# Calc_V1.net
KiCad netlist of a schematic drawn in Altium Designer
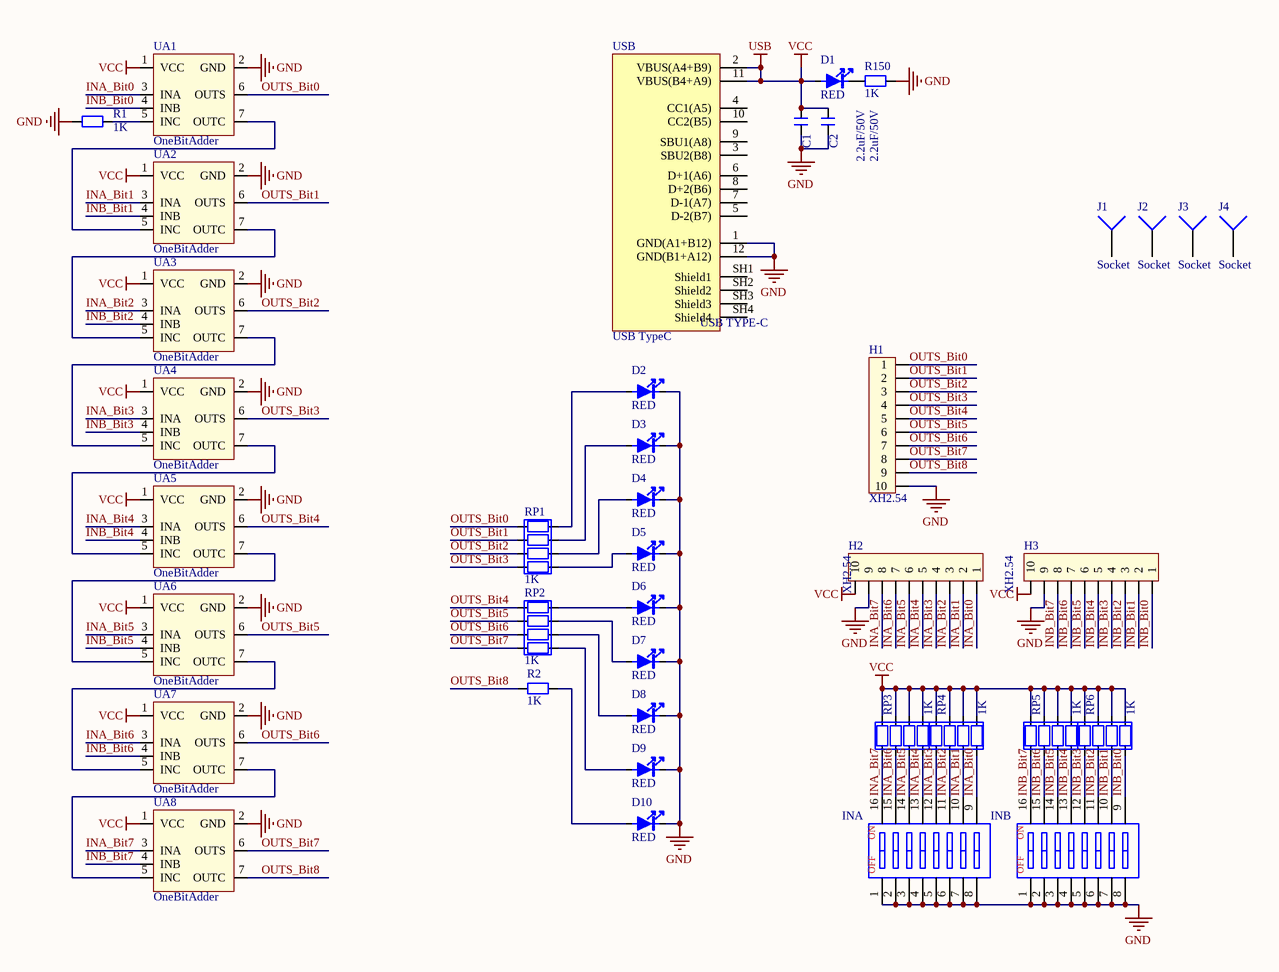
[diagram p0: Calc_V1.SchDoc]

(export (version "E")
  (design (tool "Eeschema 10.0.6"))
  (components
    (comp (ref "C1")
      (value "2.2uF/50V")
      (footprint "C 0603_L")
      (description "无极性贴片电容")
      (libsource (lib "LovelessingSch") (part "C"))
    )
    (comp (ref "C2")
      (value "2.2uF/50V")
      (footprint "C 0603_L")
      (description "无极性贴片电容")
      (libsource (lib "LovelessingSch") (part "C"))
    )
    (comp (ref "D1")
      (value "RED")
      (footprint "LED 0603B")
      (description "发光二极管")
      (libsource (lib "LovelessingSch") (part "LED"))
    )
    (comp (ref "D2")
      (value "RED")
      (footprint "LED 0603B")
      (description "发光二极管")
      (libsource (lib "LovelessingSch") (part "LED"))
    )
    (comp (ref "D3")
      (value "RED")
      (footprint "LED 0603B")
      (description "发光二极管")
      (libsource (lib "LovelessingSch") (part "LED"))
    )
    (comp (ref "D4")
      (value "RED")
      (footprint "LED 0603B")
      (description "发光二极管")
      (libsource (lib "LovelessingSch") (part "LED"))
    )
    (comp (ref "D5")
      (value "RED")
      (footprint "LED 0603B")
      (description "发光二极管")
      (libsource (lib "LovelessingSch") (part "LED"))
    )
    (comp (ref "D6")
      (value "RED")
      (footprint "LED 0603B")
      (description "发光二极管")
      (libsource (lib "LovelessingSch") (part "LED"))
    )
    (comp (ref "D7")
      (value "RED")
      (footprint "LED 0603B")
      (description "发光二极管")
      (libsource (lib "LovelessingSch") (part "LED"))
    )
    (comp (ref "D8")
      (value "RED")
      (footprint "LED 0603B")
      (description "发光二极管")
      (libsource (lib "LovelessingSch") (part "LED"))
    )
    (comp (ref "D9")
      (value "RED")
      (footprint "LED 0603B")
      (description "发光二极管")
      (libsource (lib "LovelessingSch") (part "LED"))
    )
    (comp (ref "D10")
      (value "RED")
      (footprint "LED 0603B")
      (description "发光二极管")
      (libsource (lib "LovelessingSch") (part "LED"))
    )
    (comp (ref "H1")
      (value "XH2.54")
      (footprint "HDR2.54-LI-10P")
      (description "端子")
      (libsource (lib "") (part "Header_10P_1"))
    )
    (comp (ref "H2")
      (value "XH2.54")
      (footprint "HDR2.54-LI-10P")
      (description "端子")
      (libsource (lib "LovelessingSch") (part "Header_10P"))
    )
    (comp (ref "H3")
      (value "XH2.54")
      (footprint "HDR2.54-LI-10P")
      (description "端子")
      (libsource (lib "LovelessingSch") (part "Header_10P"))
    )
    (comp (ref "INA")
      (value "CSW-8P")
      (footprint "CSW DIP-8P")
      (description "8路编码开关")
      (libsource (lib "LovelessingSch") (part "CSW-8P"))
    )
    (comp (ref "INB")
      (value "CSW-8P")
      (footprint "CSW DIP-8P")
      (description "8路编码开关")
      (libsource (lib "LovelessingSch") (part "CSW-8P"))
    )
    (comp (ref "J1")
      (value "Socket")
      (footprint "M3")
      (fields (field (name "PUBLISHER") "Altium Limited"))
      (libsource (lib "Miscellaneous Connectors") (part "Socket"))
    )
    (comp (ref "J2")
      (value "Socket")
      (footprint "M3")
      (fields (field (name "PUBLISHER") "Altium Limited"))
      (libsource (lib "Miscellaneous Connectors") (part "Socket"))
    )
    (comp (ref "J3")
      (value "Socket")
      (footprint "M3")
      (fields (field (name "PUBLISHER") "Altium Limited"))
      (libsource (lib "Miscellaneous Connectors") (part "Socket"))
    )
    (comp (ref "J4")
      (value "Socket")
      (footprint "M3")
      (fields (field (name "PUBLISHER") "Altium Limited"))
      (libsource (lib "Miscellaneous Connectors") (part "Socket"))
    )
    (comp (ref "R1")
      (value "1K")
      (footprint "R 0603_L")
      (description "贴片电阻")
      (libsource (lib "LovelessingSch") (part "R"))
    )
    (comp (ref "R2")
      (value "1K")
      (footprint "R 0603_L")
      (description "贴片电阻")
      (libsource (lib "LovelessingSch") (part "R"))
    )
    (comp (ref "R150")
      (value "1K")
      (footprint "R 0603_L")
      (description "贴片电阻")
      (libsource (lib "LovelessingSch") (part "R"))
    )
    (comp (ref "RP1")
      (value "1K")
      (footprint "P_pack")
      (description "贴片排阻")
      (libsource (lib "") (part "R_pack_1"))
    )
    (comp (ref "RP2")
      (value "1K")
      (footprint "P_pack")
      (description "贴片排阻")
      (libsource (lib "") (part "R_pack_1"))
    )
    (comp (ref "RP3")
      (value "1K")
      (footprint "P_pack")
      (description "贴片排阻")
      (libsource (lib "LovelessingSch") (part "R_pack"))
    )
    (comp (ref "RP4")
      (value "1K")
      (footprint "P_pack")
      (description "贴片排阻")
      (libsource (lib "LovelessingSch") (part "R_pack"))
    )
    (comp (ref "RP5")
      (value "1K")
      (footprint "P_pack")
      (description "贴片排阻")
      (libsource (lib "LovelessingSch") (part "R_pack"))
    )
    (comp (ref "RP6")
      (value "1K")
      (footprint "P_pack")
      (description "贴片排阻")
      (libsource (lib "LovelessingSch") (part "R_pack"))
    )
    (comp (ref "UA1")
      (value "OneBitAdder")
      (footprint "OneBitAdder")
      (description "一位全加法器")
      (libsource (lib "Schlib1") (part "OneBitAdder"))
    )
    (comp (ref "UA2")
      (value "OneBitAdder")
      (footprint "OneBitAdder")
      (description "一位全加法器")
      (libsource (lib "Schlib1") (part "OneBitAdder"))
    )
    (comp (ref "UA3")
      (value "OneBitAdder")
      (footprint "OneBitAdder")
      (description "一位全加法器")
      (libsource (lib "Schlib1") (part "OneBitAdder"))
    )
    (comp (ref "UA4")
      (value "OneBitAdder")
      (footprint "OneBitAdder")
      (description "一位全加法器")
      (libsource (lib "Schlib1") (part "OneBitAdder"))
    )
    (comp (ref "UA5")
      (value "OneBitAdder")
      (footprint "OneBitAdder")
      (description "一位全加法器")
      (libsource (lib "Schlib1") (part "OneBitAdder"))
    )
    (comp (ref "UA6")
      (value "OneBitAdder")
      (footprint "OneBitAdder")
      (description "一位全加法器")
      (libsource (lib "Schlib1") (part "OneBitAdder"))
    )
    (comp (ref "UA7")
      (value "OneBitAdder")
      (footprint "OneBitAdder")
      (description "一位全加法器")
      (libsource (lib "Schlib1") (part "OneBitAdder"))
    )
    (comp (ref "UA8")
      (value "OneBitAdder")
      (footprint "OneBitAdder")
      (description "一位全加法器")
      (libsource (lib "Schlib1") (part "OneBitAdder"))
    )
    (comp (ref "USB")
      (value "USB TypeC")
      (footprint "USB Type-C")
      (description "12P TypeC 母座")
      (fields (field (name "版权归属") "正点原子"))
      (libsource (lib "正点原子封装库V1.0") (part "USB 2.0 Type C"))
    )
  )
  (nets
    (net (code "1") (name "/INA_Bit0") (class "Default")
      (node (ref "H2") (pin "1") (pinfunction "1_1") (pintype "passive"))
      (node (ref "INA") (pin "9") (pinfunction "9_9") (pintype "passive"))
      (node (ref "RP4") (pin "7") (pinfunction "7_7") (pintype "passive"))
      (node (ref "UA1") (pin "3") (pinfunction "INA_3") (pintype "passive"))
    )
    (net (code "2") (name "/INA_Bit1") (class "Default")
      (node (ref "H2") (pin "2") (pinfunction "2_2") (pintype "passive"))
      (node (ref "INA") (pin "10") (pinfunction "10_10") (pintype "passive"))
      (node (ref "RP4") (pin "5") (pinfunction "5_5") (pintype "passive"))
      (node (ref "UA2") (pin "3") (pinfunction "INA_3") (pintype "passive"))
    )
    (net (code "3") (name "/INA_Bit2") (class "Default")
      (node (ref "H2") (pin "3") (pinfunction "3_3") (pintype "passive"))
      (node (ref "INA") (pin "11") (pinfunction "11_11") (pintype "passive"))
      (node (ref "RP4") (pin "3") (pinfunction "3_3") (pintype "passive"))
      (node (ref "UA3") (pin "3") (pinfunction "INA_3") (pintype "passive"))
    )
    (net (code "4") (name "/INA_Bit3") (class "Default")
      (node (ref "H2") (pin "4") (pinfunction "4_4") (pintype "passive"))
      (node (ref "INA") (pin "12") (pinfunction "12_12") (pintype "passive"))
      (node (ref "RP4") (pin "1") (pinfunction "1_1") (pintype "passive"))
      (node (ref "UA4") (pin "3") (pinfunction "INA_3") (pintype "passive"))
    )
    (net (code "5") (name "/INA_Bit4") (class "Default")
      (node (ref "H2") (pin "5") (pinfunction "5_5") (pintype "passive"))
      (node (ref "INA") (pin "13") (pinfunction "13_13") (pintype "passive"))
      (node (ref "RP3") (pin "7") (pinfunction "7_7") (pintype "passive"))
      (node (ref "UA5") (pin "3") (pinfunction "INA_3") (pintype "passive"))
    )
    (net (code "6") (name "/INA_Bit5") (class "Default")
      (node (ref "H2") (pin "6") (pinfunction "6_6") (pintype "passive"))
      (node (ref "INA") (pin "14") (pinfunction "14_14") (pintype "passive"))
      (node (ref "RP3") (pin "5") (pinfunction "5_5") (pintype "passive"))
      (node (ref "UA6") (pin "3") (pinfunction "INA_3") (pintype "passive"))
    )
    (net (code "7") (name "/INA_Bit6") (class "Default")
      (node (ref "H2") (pin "7") (pinfunction "7_7") (pintype "passive"))
      (node (ref "INA") (pin "15") (pinfunction "15_15") (pintype "passive"))
      (node (ref "RP3") (pin "3") (pinfunction "3_3") (pintype "passive"))
      (node (ref "UA7") (pin "3") (pinfunction "INA_3") (pintype "passive"))
    )
    (net (code "8") (name "/INA_Bit7") (class "Default")
      (node (ref "H2") (pin "8") (pinfunction "8_8") (pintype "passive"))
      (node (ref "INA") (pin "16") (pinfunction "16_16") (pintype "passive"))
      (node (ref "RP3") (pin "1") (pinfunction "1_1") (pintype "passive"))
      (node (ref "UA8") (pin "3") (pinfunction "INA_3") (pintype "passive"))
    )
    (net (code "9") (name "/INB_Bit0") (class "Default")
      (node (ref "H3") (pin "1") (pinfunction "1_1") (pintype "passive"))
      (node (ref "INB") (pin "9") (pinfunction "9_9") (pintype "passive"))
      (node (ref "RP6") (pin "7") (pinfunction "7_7") (pintype "passive"))
      (node (ref "UA1") (pin "4") (pinfunction "INB_4") (pintype "passive"))
    )
    (net (code "10") (name "/INB_Bit1") (class "Default")
      (node (ref "H3") (pin "2") (pinfunction "2_2") (pintype "passive"))
      (node (ref "INB") (pin "10") (pinfunction "10_10") (pintype "passive"))
      (node (ref "RP6") (pin "5") (pinfunction "5_5") (pintype "passive"))
      (node (ref "UA2") (pin "4") (pinfunction "INB_4") (pintype "passive"))
    )
    (net (code "11") (name "/INB_Bit2") (class "Default")
      (node (ref "H3") (pin "3") (pinfunction "3_3") (pintype "passive"))
      (node (ref "INB") (pin "11") (pinfunction "11_11") (pintype "passive"))
      (node (ref "RP6") (pin "3") (pinfunction "3_3") (pintype "passive"))
      (node (ref "UA3") (pin "4") (pinfunction "INB_4") (pintype "passive"))
    )
    (net (code "12") (name "/INB_Bit3") (class "Default")
      (node (ref "H3") (pin "4") (pinfunction "4_4") (pintype "passive"))
      (node (ref "INB") (pin "12") (pinfunction "12_12") (pintype "passive"))
      (node (ref "RP6") (pin "1") (pinfunction "1_1") (pintype "passive"))
      (node (ref "UA4") (pin "4") (pinfunction "INB_4") (pintype "passive"))
    )
    (net (code "13") (name "/INB_Bit4") (class "Default")
      (node (ref "H3") (pin "5") (pinfunction "5_5") (pintype "passive"))
      (node (ref "INB") (pin "13") (pinfunction "13_13") (pintype "passive"))
      (node (ref "RP5") (pin "7") (pinfunction "7_7") (pintype "passive"))
      (node (ref "UA5") (pin "4") (pinfunction "INB_4") (pintype "passive"))
    )
    (net (code "14") (name "/INB_Bit5") (class "Default")
      (node (ref "H3") (pin "6") (pinfunction "6_6") (pintype "passive"))
      (node (ref "INB") (pin "14") (pinfunction "14_14") (pintype "passive"))
      (node (ref "RP5") (pin "5") (pinfunction "5_5") (pintype "passive"))
      (node (ref "UA6") (pin "4") (pinfunction "INB_4") (pintype "passive"))
    )
    (net (code "15") (name "/INB_Bit6") (class "Default")
      (node (ref "H3") (pin "7") (pinfunction "7_7") (pintype "passive"))
      (node (ref "INB") (pin "15") (pinfunction "15_15") (pintype "passive"))
      (node (ref "RP5") (pin "3") (pinfunction "3_3") (pintype "passive"))
      (node (ref "UA7") (pin "4") (pinfunction "INB_4") (pintype "passive"))
    )
    (net (code "16") (name "/INB_Bit7") (class "Default")
      (node (ref "H3") (pin "8") (pinfunction "8_8") (pintype "passive"))
      (node (ref "INB") (pin "16") (pinfunction "16_16") (pintype "passive"))
      (node (ref "RP5") (pin "1") (pinfunction "1_1") (pintype "passive"))
      (node (ref "UA8") (pin "4") (pinfunction "INB_4") (pintype "passive"))
    )
    (net (code "17") (name "/OUTS_Bit0") (class "Default")
      (node (ref "H1") (pin "1") (pinfunction "1_1") (pintype "passive"))
      (node (ref "RP1") (pin "2") (pinfunction "2_2") (pintype "passive"))
      (node (ref "UA1") (pin "6") (pinfunction "OUTS_6") (pintype "passive"))
    )
    (net (code "18") (name "/OUTS_Bit1") (class "Default")
      (node (ref "H1") (pin "2") (pinfunction "2_2") (pintype "passive"))
      (node (ref "RP1") (pin "4") (pinfunction "4_4") (pintype "passive"))
      (node (ref "UA2") (pin "6") (pinfunction "OUTS_6") (pintype "passive"))
    )
    (net (code "19") (name "/OUTS_Bit2") (class "Default")
      (node (ref "H1") (pin "3") (pinfunction "3_3") (pintype "passive"))
      (node (ref "RP1") (pin "6") (pinfunction "6_6") (pintype "passive"))
      (node (ref "UA3") (pin "6") (pinfunction "OUTS_6") (pintype "passive"))
    )
    (net (code "20") (name "/OUTS_Bit3") (class "Default")
      (node (ref "H1") (pin "4") (pinfunction "4_4") (pintype "passive"))
      (node (ref "RP1") (pin "8") (pinfunction "8_8") (pintype "passive"))
      (node (ref "UA4") (pin "6") (pinfunction "OUTS_6") (pintype "passive"))
    )
    (net (code "21") (name "/OUTS_Bit4") (class "Default")
      (node (ref "H1") (pin "5") (pinfunction "5_5") (pintype "passive"))
      (node (ref "RP2") (pin "2") (pinfunction "2_2") (pintype "passive"))
      (node (ref "UA5") (pin "6") (pinfunction "OUTS_6") (pintype "passive"))
    )
    (net (code "22") (name "/OUTS_Bit5") (class "Default")
      (node (ref "H1") (pin "6") (pinfunction "6_6") (pintype "passive"))
      (node (ref "RP2") (pin "4") (pinfunction "4_4") (pintype "passive"))
      (node (ref "UA6") (pin "6") (pinfunction "OUTS_6") (pintype "passive"))
    )
    (net (code "23") (name "/OUTS_Bit6") (class "Default")
      (node (ref "H1") (pin "7") (pinfunction "7_7") (pintype "passive"))
      (node (ref "RP2") (pin "6") (pinfunction "6_6") (pintype "passive"))
      (node (ref "UA7") (pin "6") (pinfunction "OUTS_6") (pintype "passive"))
    )
    (net (code "24") (name "/OUTS_Bit7") (class "Default")
      (node (ref "H1") (pin "8") (pinfunction "8_8") (pintype "passive"))
      (node (ref "RP2") (pin "8") (pinfunction "8_8") (pintype "passive"))
      (node (ref "UA8") (pin "6") (pinfunction "OUTS_6") (pintype "passive"))
    )
    (net (code "25") (name "/OUTS_Bit8") (class "Default")
      (node (ref "H1") (pin "9") (pinfunction "9_9") (pintype "passive"))
      (node (ref "R2") (pin "1") (pinfunction "1_1") (pintype "passive"))
      (node (ref "UA8") (pin "7") (pinfunction "OUTC_7") (pintype "passive"))
    )
    (net (code "26") (name "GND") (class "Default")
      (node (ref "C1") (pin "1") (pinfunction "1_1") (pintype "passive"))
      (node (ref "C2") (pin "1") (pinfunction "1_1") (pintype "passive"))
      (node (ref "D10") (pin "2") (pinfunction "2_2") (pintype "passive"))
      (node (ref "D2") (pin "2") (pinfunction "2_2") (pintype "passive"))
      (node (ref "D3") (pin "2") (pinfunction "2_2") (pintype "passive"))
      (node (ref "D4") (pin "2") (pinfunction "2_2") (pintype "passive"))
      (node (ref "D5") (pin "2") (pinfunction "2_2") (pintype "passive"))
      (node (ref "D6") (pin "2") (pinfunction "2_2") (pintype "passive"))
      (node (ref "D7") (pin "2") (pinfunction "2_2") (pintype "passive"))
      (node (ref "D8") (pin "2") (pinfunction "2_2") (pintype "passive"))
      (node (ref "D9") (pin "2") (pinfunction "2_2") (pintype "passive"))
      (node (ref "H1") (pin "10") (pinfunction "10_10") (pintype "passive"))
      (node (ref "H2") (pin "9") (pinfunction "9_9") (pintype "passive"))
      (node (ref "H3") (pin "9") (pinfunction "9_9") (pintype "passive"))
      (node (ref "INA") (pin "1") (pinfunction "1_1") (pintype "passive"))
      (node (ref "INA") (pin "2") (pinfunction "2_2") (pintype "passive"))
      (node (ref "INA") (pin "3") (pinfunction "3_3") (pintype "passive"))
      (node (ref "INA") (pin "4") (pinfunction "4_4") (pintype "passive"))
      (node (ref "INA") (pin "5") (pinfunction "5_5") (pintype "passive"))
      (node (ref "INA") (pin "6") (pinfunction "6_6") (pintype "passive"))
      (node (ref "INA") (pin "7") (pinfunction "7_7") (pintype "passive"))
      (node (ref "INA") (pin "8") (pinfunction "8_8") (pintype "passive"))
      (node (ref "INB") (pin "1") (pinfunction "1_1") (pintype "passive"))
      (node (ref "INB") (pin "2") (pinfunction "2_2") (pintype "passive"))
      (node (ref "INB") (pin "3") (pinfunction "3_3") (pintype "passive"))
      (node (ref "INB") (pin "4") (pinfunction "4_4") (pintype "passive"))
      (node (ref "INB") (pin "5") (pinfunction "5_5") (pintype "passive"))
      (node (ref "INB") (pin "6") (pinfunction "6_6") (pintype "passive"))
      (node (ref "INB") (pin "7") (pinfunction "7_7") (pintype "passive"))
      (node (ref "INB") (pin "8") (pinfunction "8_8") (pintype "passive"))
      (node (ref "R1") (pin "1") (pinfunction "1_1") (pintype "passive"))
      (node (ref "R150") (pin "2") (pinfunction "2_2") (pintype "passive"))
      (node (ref "UA1") (pin "2") (pinfunction "GND_2") (pintype "passive"))
      (node (ref "UA2") (pin "2") (pinfunction "GND_2") (pintype "passive"))
      (node (ref "UA3") (pin "2") (pinfunction "GND_2") (pintype "passive"))
      (node (ref "UA4") (pin "2") (pinfunction "GND_2") (pintype "passive"))
      (node (ref "UA5") (pin "2") (pinfunction "GND_2") (pintype "passive"))
      (node (ref "UA6") (pin "2") (pinfunction "GND_2") (pintype "passive"))
      (node (ref "UA7") (pin "2") (pinfunction "GND_2") (pintype "passive"))
      (node (ref "UA8") (pin "2") (pinfunction "GND_2") (pintype "passive"))
      (node (ref "USB") (pin "1") (pinfunction "GND(A1+B12)_1") (pintype "passive"))
      (node (ref "USB") (pin "12") (pinfunction "GND(B1+A12)_12") (pintype "passive"))
    )
    (net (code "27") (name "Net-(D1-Pad2)") (class "Default")
      (node (ref "D1") (pin "2") (pinfunction "2_2") (pintype "passive"))
      (node (ref "R150") (pin "1") (pinfunction "1_1") (pintype "passive"))
    )
    (net (code "28") (name "Net-(D2-Pad1)") (class "Default")
      (node (ref "D2") (pin "1") (pinfunction "1_1") (pintype "passive"))
      (node (ref "RP1") (pin "1") (pinfunction "1_1") (pintype "passive"))
    )
    (net (code "29") (name "Net-(D3-Pad1)") (class "Default")
      (node (ref "D3") (pin "1") (pinfunction "1_1") (pintype "passive"))
      (node (ref "RP1") (pin "3") (pinfunction "3_3") (pintype "passive"))
    )
    (net (code "30") (name "Net-(D4-Pad1)") (class "Default")
      (node (ref "D4") (pin "1") (pinfunction "1_1") (pintype "passive"))
      (node (ref "RP1") (pin "5") (pinfunction "5_5") (pintype "passive"))
    )
    (net (code "31") (name "Net-(D5-Pad1)") (class "Default")
      (node (ref "D5") (pin "1") (pinfunction "1_1") (pintype "passive"))
      (node (ref "RP1") (pin "7") (pinfunction "7_7") (pintype "passive"))
    )
    (net (code "32") (name "Net-(D6-Pad1)") (class "Default")
      (node (ref "D6") (pin "1") (pinfunction "1_1") (pintype "passive"))
      (node (ref "RP2") (pin "1") (pinfunction "1_1") (pintype "passive"))
    )
    (net (code "33") (name "Net-(D7-Pad1)") (class "Default")
      (node (ref "D7") (pin "1") (pinfunction "1_1") (pintype "passive"))
      (node (ref "RP2") (pin "3") (pinfunction "3_3") (pintype "passive"))
    )
    (net (code "34") (name "Net-(D8-Pad1)") (class "Default")
      (node (ref "D8") (pin "1") (pinfunction "1_1") (pintype "passive"))
      (node (ref "RP2") (pin "5") (pinfunction "5_5") (pintype "passive"))
    )
    (net (code "35") (name "Net-(D9-Pad1)") (class "Default")
      (node (ref "D9") (pin "1") (pinfunction "1_1") (pintype "passive"))
      (node (ref "RP2") (pin "7") (pinfunction "7_7") (pintype "passive"))
    )
    (net (code "36") (name "Net-(D10-Pad1)") (class "Default")
      (node (ref "D10") (pin "1") (pinfunction "1_1") (pintype "passive"))
      (node (ref "R2") (pin "2") (pinfunction "2_2") (pintype "passive"))
    )
    (net (code "37") (name "Net-(UA1-INC)") (class "Default")
      (node (ref "R1") (pin "2") (pinfunction "2_2") (pintype "passive"))
      (node (ref "UA1") (pin "5") (pinfunction "INC_5") (pintype "passive"))
    )
    (net (code "38") (name "Net-(UA1-OUTC)") (class "Default")
      (node (ref "UA1") (pin "7") (pinfunction "OUTC_7") (pintype "passive"))
      (node (ref "UA2") (pin "5") (pinfunction "INC_5") (pintype "passive"))
    )
    (net (code "39") (name "Net-(UA2-OUTC)") (class "Default")
      (node (ref "UA2") (pin "7") (pinfunction "OUTC_7") (pintype "passive"))
      (node (ref "UA3") (pin "5") (pinfunction "INC_5") (pintype "passive"))
    )
    (net (code "40") (name "Net-(UA3-OUTC)") (class "Default")
      (node (ref "UA3") (pin "7") (pinfunction "OUTC_7") (pintype "passive"))
      (node (ref "UA4") (pin "5") (pinfunction "INC_5") (pintype "passive"))
    )
    (net (code "41") (name "Net-(UA4-OUTC)") (class "Default")
      (node (ref "UA4") (pin "7") (pinfunction "OUTC_7") (pintype "passive"))
      (node (ref "UA5") (pin "5") (pinfunction "INC_5") (pintype "passive"))
    )
    (net (code "42") (name "Net-(UA5-OUTC)") (class "Default")
      (node (ref "UA5") (pin "7") (pinfunction "OUTC_7") (pintype "passive"))
      (node (ref "UA6") (pin "5") (pinfunction "INC_5") (pintype "passive"))
    )
    (net (code "43") (name "Net-(UA6-OUTC)") (class "Default")
      (node (ref "UA6") (pin "7") (pinfunction "OUTC_7") (pintype "passive"))
      (node (ref "UA7") (pin "5") (pinfunction "INC_5") (pintype "passive"))
    )
    (net (code "44") (name "Net-(UA7-OUTC)") (class "Default")
      (node (ref "UA7") (pin "7") (pinfunction "OUTC_7") (pintype "passive"))
      (node (ref "UA8") (pin "5") (pinfunction "INC_5") (pintype "passive"))
    )
    (net (code "45") (name "USB") (class "Default")
      (node (ref "C1") (pin "2") (pinfunction "2_2") (pintype "passive"))
      (node (ref "C2") (pin "2") (pinfunction "2_2") (pintype "passive"))
      (node (ref "D1") (pin "1") (pinfunction "1_1") (pintype "passive"))
      (node (ref "H2") (pin "10") (pinfunction "10_10") (pintype "passive"))
      (node (ref "H3") (pin "10") (pinfunction "10_10") (pintype "passive"))
      (node (ref "RP3") (pin "2") (pinfunction "2_2") (pintype "passive"))
      (node (ref "RP3") (pin "4") (pinfunction "4_4") (pintype "passive"))
      (node (ref "RP3") (pin "6") (pinfunction "6_6") (pintype "passive"))
      (node (ref "RP3") (pin "8") (pinfunction "8_8") (pintype "passive"))
      (node (ref "RP4") (pin "2") (pinfunction "2_2") (pintype "passive"))
      (node (ref "RP4") (pin "4") (pinfunction "4_4") (pintype "passive"))
      (node (ref "RP4") (pin "6") (pinfunction "6_6") (pintype "passive"))
      (node (ref "RP4") (pin "8") (pinfunction "8_8") (pintype "passive"))
      (node (ref "RP5") (pin "2") (pinfunction "2_2") (pintype "passive"))
      (node (ref "RP5") (pin "4") (pinfunction "4_4") (pintype "passive"))
      (node (ref "RP5") (pin "6") (pinfunction "6_6") (pintype "passive"))
      (node (ref "RP5") (pin "8") (pinfunction "8_8") (pintype "passive"))
      (node (ref "RP6") (pin "2") (pinfunction "2_2") (pintype "passive"))
      (node (ref "RP6") (pin "4") (pinfunction "4_4") (pintype "passive"))
      (node (ref "RP6") (pin "6") (pinfunction "6_6") (pintype "passive"))
      (node (ref "RP6") (pin "8") (pinfunction "8_8") (pintype "passive"))
      (node (ref "UA1") (pin "1") (pinfunction "VCC_1") (pintype "passive"))
      (node (ref "UA2") (pin "1") (pinfunction "VCC_1") (pintype "passive"))
      (node (ref "UA3") (pin "1") (pinfunction "VCC_1") (pintype "passive"))
      (node (ref "UA4") (pin "1") (pinfunction "VCC_1") (pintype "passive"))
      (node (ref "UA5") (pin "1") (pinfunction "VCC_1") (pintype "passive"))
      (node (ref "UA6") (pin "1") (pinfunction "VCC_1") (pintype "passive"))
      (node (ref "UA7") (pin "1") (pinfunction "VCC_1") (pintype "passive"))
      (node (ref "UA8") (pin "1") (pinfunction "VCC_1") (pintype "passive"))
      (node (ref "USB") (pin "11") (pinfunction "VBUS(B4+A9)_11") (pintype "passive"))
      (node (ref "USB") (pin "2") (pinfunction "VBUS(A4+B9)_2") (pintype "passive"))
    )
    (net (code "46") (name "unconnected-(J1-Pad1)") (class "Default")
      (node (ref "J1") (pin "1") (pinfunction "1_1") (pintype "passive"))
    )
    (net (code "47") (name "unconnected-(J2-Pad1)") (class "Default")
      (node (ref "J2") (pin "1") (pinfunction "1_1") (pintype "passive"))
    )
    (net (code "48") (name "unconnected-(J3-Pad1)") (class "Default")
      (node (ref "J3") (pin "1") (pinfunction "1_1") (pintype "passive"))
    )
    (net (code "49") (name "unconnected-(J4-Pad1)") (class "Default")
      (node (ref "J4") (pin "1") (pinfunction "1_1") (pintype "passive"))
    )
    (net (code "50") (name "unconnected-(USB-CC1(A5)-Pad4)") (class "Default")
      (node (ref "USB") (pin "4") (pinfunction "CC1(A5)_4") (pintype "passive"))
    )
    (net (code "51") (name "unconnected-(USB-CC2(B5)-Pad10)") (class "Default")
      (node (ref "USB") (pin "10") (pinfunction "CC2(B5)_10") (pintype "passive"))
    )
    (net (code "52") (name "unconnected-(USB-D+1(A6)-Pad6)") (class "Default")
      (node (ref "USB") (pin "6") (pinfunction "D+1(A6)_6") (pintype "passive"))
    )
    (net (code "53") (name "unconnected-(USB-D+2(B6)-Pad8)") (class "Default")
      (node (ref "USB") (pin "8") (pinfunction "D+2(B6)_8") (pintype "passive"))
    )
    (net (code "54") (name "unconnected-(USB-D-1(A7)-Pad7)") (class "Default")
      (node (ref "USB") (pin "7") (pinfunction "D-1(A7)_7") (pintype "passive"))
    )
    (net (code "55") (name "unconnected-(USB-D-2(B7)-Pad5)") (class "Default")
      (node (ref "USB") (pin "5") (pinfunction "D-2(B7)_5") (pintype "passive"))
    )
    (net (code "56") (name "unconnected-(USB-SBU1(A8)-Pad9)") (class "Default")
      (node (ref "USB") (pin "9") (pinfunction "SBU1(A8)_9") (pintype "passive"))
    )
    (net (code "57") (name "unconnected-(USB-SBU2(B8)-Pad3)") (class "Default")
      (node (ref "USB") (pin "3") (pinfunction "SBU2(B8)_3") (pintype "passive"))
    )
    (net (code "58") (name "unconnected-(USB-Shield1-PadSH1)") (class "Default")
      (node (ref "USB") (pin "SH1") (pinfunction "Shield1_SH1") (pintype "passive"))
    )
    (net (code "59") (name "unconnected-(USB-Shield2-PadSH2)") (class "Default")
      (node (ref "USB") (pin "SH2") (pinfunction "Shield2_SH2") (pintype "passive"))
    )
    (net (code "60") (name "unconnected-(USB-Shield3-PadSH3)") (class "Default")
      (node (ref "USB") (pin "SH3") (pinfunction "Shield3_SH3") (pintype "passive"))
    )
    (net (code "61") (name "unconnected-(USB-Shield4-PadSH4)") (class "Default")
      (node (ref "USB") (pin "SH4") (pinfunction "Shield4_SH4") (pintype "passive"))
    )
  )
)
